# ESP32_BioReactor_v1.net
KiCad netlist of a schematic drawn in EAGLE
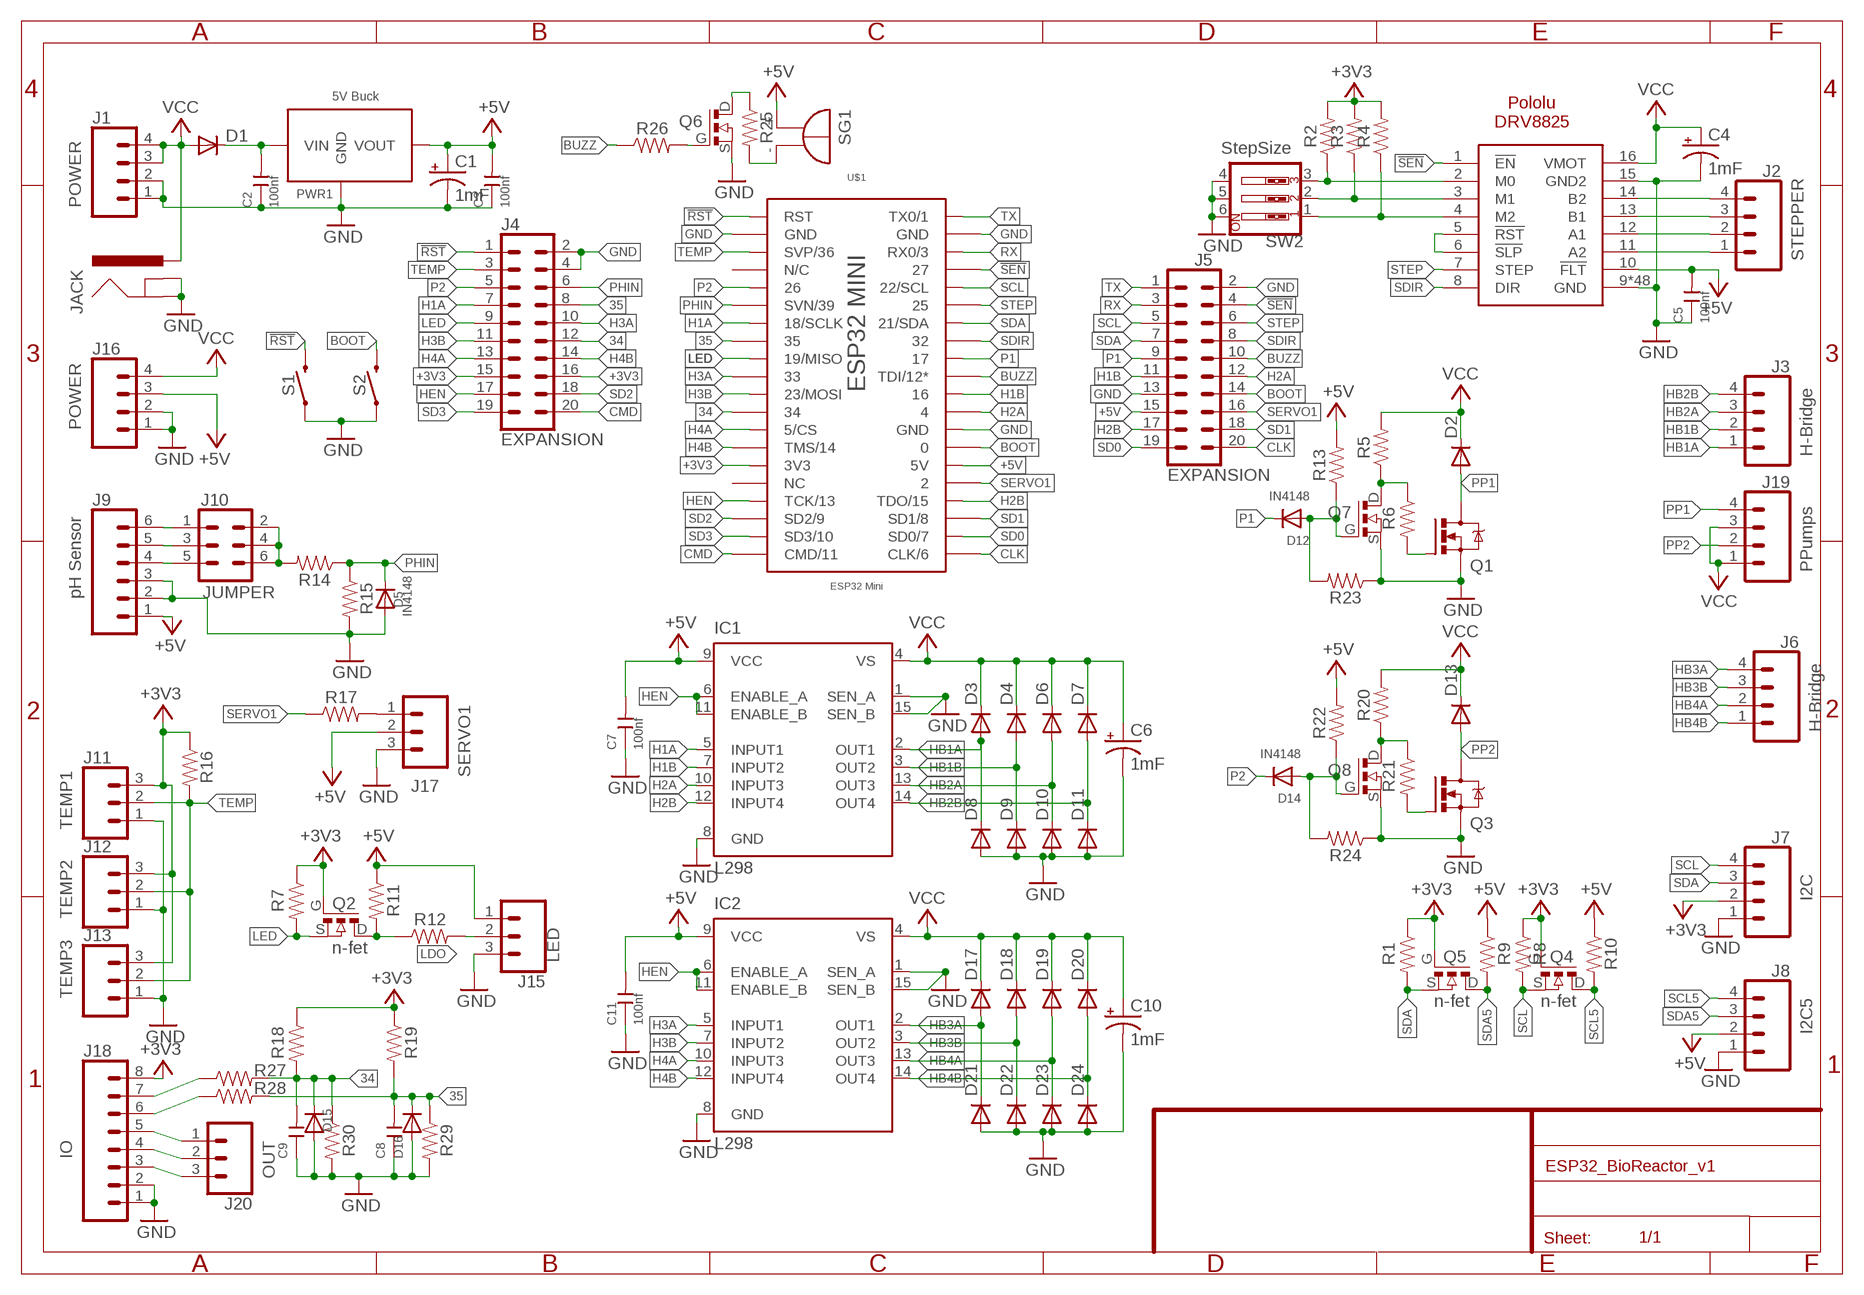
[diagram p0: schematic, sheet 1]

(export (version "E")
  (design (tool "Eeschema 10.0.6"))
  (components
    (comp (ref "C1")
      (value "1mF")
      (footprint "eagle-import:CPOL-RADIAL-5MM-10MM")
      (libsource (lib "eagle-import") (part "1000UF-RADIAL-5MM-25V-20%"))
    )
    (comp (ref "C2")
      (value "100nf")
      (footprint "eagle-import:CERAMIC-2.54")
      (fields (field (name "MPN") "CC1-F5SL2A101KSPW"))
      (libsource (lib "eagle-import") (part "DIP-CERAMIC-DISC-100NF-50V-Y5V(D5.0MM)"))
    )
    (comp (ref "C3")
      (value "100nf")
      (footprint "eagle-import:CERAMIC-2.54")
      (fields (field (name "MPN") "CC1-F5SL2A101KSPW"))
      (libsource (lib "eagle-import") (part "DIP-CERAMIC-DISC-100NF-50V-Y5V(D5.0MM)"))
    )
    (comp (ref "C4")
      (value "1mF")
      (footprint "eagle-import:CPOL-RADIAL-5MM-10MM")
      (libsource (lib "eagle-import") (part "1000UF-RADIAL-5MM-25V-20%"))
    )
    (comp (ref "C5")
      (value "100nf")
      (footprint "eagle-import:CERAMIC-2.54")
      (fields (field (name "MPN") "CC1-F5SL2A101KSPW"))
      (libsource (lib "eagle-import") (part "DIP-CERAMIC-DISC-100NF-50V-Y5V(D5.0MM)"))
    )
    (comp (ref "C6")
      (value "1mF")
      (footprint "eagle-import:CPOL-RADIAL-5MM-10MM")
      (libsource (lib "eagle-import") (part "1000UF-RADIAL-5MM-25V-20%"))
    )
    (comp (ref "C7")
      (value "100nf")
      (footprint "eagle-import:CERAMIC-2.54")
      (fields (field (name "MPN") "CC1-F5SL2A101KSPW"))
      (libsource (lib "eagle-import") (part "DIP-CERAMIC-DISC-100NF-50V-Y5V(D5.0MM)"))
    )
    (comp (ref "C8")
      (value "100nf")
      (footprint "eagle-import:CERAMIC-2.54")
      (fields (field (name "MPN") "CC1-F5SL2A101KSPW"))
      (libsource (lib "eagle-import") (part "DIP-CERAMIC-DISC-100NF-50V-Y5V(D5.0MM)"))
    )
    (comp (ref "C9")
      (value "100nf")
      (footprint "eagle-import:CERAMIC-2.54")
      (fields (field (name "MPN") "CC1-F5SL2A101KSPW"))
      (libsource (lib "eagle-import") (part "DIP-CERAMIC-DISC-100NF-50V-Y5V(D5.0MM)"))
    )
    (comp (ref "C10")
      (value "1mF")
      (footprint "eagle-import:CPOL-RADIAL-5MM-10MM")
      (libsource (lib "eagle-import") (part "1000UF-RADIAL-5MM-25V-20%"))
    )
    (comp (ref "C11")
      (value "100nf")
      (footprint "eagle-import:CERAMIC-2.54")
      (fields (field (name "MPN") "CC1-F5SL2A101KSPW"))
      (libsource (lib "eagle-import") (part "DIP-CERAMIC-DISC-100NF-50V-Y5V(D5.0MM)"))
    )
    (comp (ref "D1")
      (value "1N4004")
      (footprint "eagle-import:DO41-10")
      (libsource (lib "eagle-import") (part "1N4004"))
    )
    (comp (ref "D2")
      (value "1N4004")
      (footprint "eagle-import:DO41-10")
      (libsource (lib "eagle-import") (part "1N4004"))
    )
    (comp (ref "D3")
      (value "1N4004")
      (footprint "eagle-import:DO41-10")
      (libsource (lib "eagle-import") (part "1N4004"))
    )
    (comp (ref "D4")
      (value "1N4004")
      (footprint "eagle-import:DO41-10")
      (libsource (lib "eagle-import") (part "1N4004"))
    )
    (comp (ref "D5")
      (value "IN4148")
      (footprint "eagle-import:DO-1N4148")
      (libsource (lib "eagle-import") (part "DIODEDO-1N4148"))
    )
    (comp (ref "D6")
      (value "1N4004")
      (footprint "eagle-import:DO41-10")
      (libsource (lib "eagle-import") (part "1N4004"))
    )
    (comp (ref "D7")
      (value "1N4004")
      (footprint "eagle-import:DO41-10")
      (libsource (lib "eagle-import") (part "1N4004"))
    )
    (comp (ref "D8")
      (value "1N4004")
      (footprint "eagle-import:DO41-10")
      (libsource (lib "eagle-import") (part "1N4004"))
    )
    (comp (ref "D9")
      (value "1N4004")
      (footprint "eagle-import:DO41-10")
      (libsource (lib "eagle-import") (part "1N4004"))
    )
    (comp (ref "D10")
      (value "1N4004")
      (footprint "eagle-import:DO41-10")
      (libsource (lib "eagle-import") (part "1N4004"))
    )
    (comp (ref "D11")
      (value "1N4004")
      (footprint "eagle-import:DO41-10")
      (libsource (lib "eagle-import") (part "1N4004"))
    )
    (comp (ref "D12")
      (value "IN4148")
      (footprint "eagle-import:DO-1N4148")
      (libsource (lib "eagle-import") (part "DIODEDO-1N4148"))
    )
    (comp (ref "D13")
      (value "1N4004")
      (footprint "eagle-import:DO41-10")
      (libsource (lib "eagle-import") (part "1N4004"))
    )
    (comp (ref "D14")
      (value "IN4148")
      (footprint "eagle-import:DO-1N4148")
      (libsource (lib "eagle-import") (part "DIODEDO-1N4148"))
    )
    (comp (ref "D15")
      (value "IN4148")
      (footprint "eagle-import:DO-1N4148")
      (libsource (lib "eagle-import") (part "DIODEDO-1N4148"))
    )
    (comp (ref "D16")
      (value "IN4148")
      (footprint "eagle-import:DO-1N4148")
      (libsource (lib "eagle-import") (part "DIODEDO-1N4148"))
    )
    (comp (ref "D17")
      (value "1N4004")
      (footprint "eagle-import:DO41-10")
      (libsource (lib "eagle-import") (part "1N4004"))
    )
    (comp (ref "D18")
      (value "1N4004")
      (footprint "eagle-import:DO41-10")
      (libsource (lib "eagle-import") (part "1N4004"))
    )
    (comp (ref "D19")
      (value "1N4004")
      (footprint "eagle-import:DO41-10")
      (libsource (lib "eagle-import") (part "1N4004"))
    )
    (comp (ref "D20")
      (value "1N4004")
      (footprint "eagle-import:DO41-10")
      (libsource (lib "eagle-import") (part "1N4004"))
    )
    (comp (ref "D21")
      (value "1N4004")
      (footprint "eagle-import:DO41-10")
      (libsource (lib "eagle-import") (part "1N4004"))
    )
    (comp (ref "D22")
      (value "1N4004")
      (footprint "eagle-import:DO41-10")
      (libsource (lib "eagle-import") (part "1N4004"))
    )
    (comp (ref "D23")
      (value "1N4004")
      (footprint "eagle-import:DO41-10")
      (libsource (lib "eagle-import") (part "1N4004"))
    )
    (comp (ref "D24")
      (value "1N4004")
      (footprint "eagle-import:DO41-10")
      (libsource (lib "eagle-import") (part "1N4004"))
    )
    (comp (ref "DR1")
      (value "DRV8825")
      (footprint "eagle-import:POLOLU-DRV8825")
      (libsource (lib "eagle-import") (part "POLOLU-DRV8825"))
    )
    (comp (ref "IC1")
      (value "L298")
      (footprint "eagle-import:MULTIWATT-15")
      (fields (field (name "MPN") "L298N"))
      (libsource (lib "eagle-import") (part "L298"))
    )
    (comp (ref "IC2")
      (value "L298")
      (footprint "eagle-import:MULTIWATT-15")
      (fields (field (name "MPN") "L298N"))
      (libsource (lib "eagle-import") (part "L298"))
    )
    (comp (ref "J1")
      (value "POWER")
      (footprint "eagle-import:1X04_LONGPADS")
      (libsource (lib "eagle-import") (part "CONN_04LONGPADS"))
    )
    (comp (ref "J2")
      (value "STEPPER")
      (footprint "eagle-import:1X04_LONGPADS")
      (libsource (lib "eagle-import") (part "CONN_04LONGPADS"))
    )
    (comp (ref "J3")
      (value "H-Bridge")
      (footprint "eagle-import:1X04_LONGPADS")
      (libsource (lib "eagle-import") (part "CONN_04LONGPADS"))
    )
    (comp (ref "J4")
      (value "EXPANSION")
      (footprint "eagle-import:2X10_NOSILK")
      (libsource (lib "eagle-import") (part "CONN_10X2NOSILK"))
    )
    (comp (ref "J5")
      (value "EXPANSION")
      (footprint "eagle-import:2X10_NOSILK")
      (libsource (lib "eagle-import") (part "CONN_10X2NOSILK"))
    )
    (comp (ref "J6")
      (value "H-Bridge")
      (footprint "eagle-import:1X04_LONGPADS")
      (libsource (lib "eagle-import") (part "CONN_04LONGPADS"))
    )
    (comp (ref "J7")
      (value "I2C")
      (footprint "eagle-import:1X04_LONGPADS")
      (libsource (lib "eagle-import") (part "CONN_04LONGPADS"))
    )
    (comp (ref "J8")
      (value "I2C5")
      (footprint "eagle-import:1X04_LONGPADS")
      (libsource (lib "eagle-import") (part "CONN_04LONGPADS"))
    )
    (comp (ref "J9")
      (value "pH Sensor")
      (footprint "eagle-import:1X06_LONGPADS")
      (libsource (lib "eagle-import") (part "CONN_06LONGPADS"))
    )
    (comp (ref "J10")
      (value "JUMPER")
      (footprint "eagle-import:2X3")
      (libsource (lib "eagle-import") (part "CONN_03X2FEMALE"))
    )
    (comp (ref "J11")
      (value "TEMP1")
      (footprint "eagle-import:1X03_LONGPADS")
      (libsource (lib "eagle-import") (part "CONN_03LONGPADS"))
    )
    (comp (ref "J12")
      (value "TEMP2")
      (footprint "eagle-import:1X03_LONGPADS")
      (libsource (lib "eagle-import") (part "CONN_03LONGPADS"))
    )
    (comp (ref "J13")
      (value "TEMP3")
      (footprint "eagle-import:1X03_LONGPADS")
      (libsource (lib "eagle-import") (part "CONN_03LONGPADS"))
    )
    (comp (ref "J15")
      (value "LED")
      (footprint "eagle-import:1X03_LONGPADS")
      (libsource (lib "eagle-import") (part "CONN_03LONGPADS"))
    )
    (comp (ref "J16")
      (value "POWER")
      (footprint "eagle-import:1X04_LONGPADS")
      (libsource (lib "eagle-import") (part "CONN_04LONGPADS"))
    )
    (comp (ref "J17")
      (value "SERVO1")
      (footprint "eagle-import:1X03_LONGPADS")
      (libsource (lib "eagle-import") (part "CONN_03LONGPADS"))
    )
    (comp (ref "J18")
      (value "IO")
      (footprint "eagle-import:1X08_LONGPADS")
      (libsource (lib "eagle-import") (part "CONN_08LONGPADS"))
    )
    (comp (ref "J19")
      (value "PPumps")
      (footprint "eagle-import:1X04_LONGPADS")
      (libsource (lib "eagle-import") (part "CONN_04LONGPADS"))
    )
    (comp (ref "J20")
      (value "OUT")
      (footprint "eagle-import:1X03")
      (libsource (lib "eagle-import") (part "CONN_03"))
    )
    (comp (ref "JACK")
      (value "POWER_JACKPTH_LOCK")
      (footprint "eagle-import:POWER_JACK_PTH_LOCK")
      (libsource (lib "eagle-import") (part "POWER_JACKPTH_LOCK"))
    )
    (comp (ref "PWR1")
      (value "5V Buck")
      (footprint "eagle-import:5VBUCK")
      (libsource (lib "eagle-import") (part "5VBUCK"))
    )
    (comp (ref "Q1")
      (value "IRF740")
      (footprint "eagle-import:TO220BV")
      (libsource (lib "eagle-import") (part "IRF740"))
    )
    (comp (ref "Q2")
      (value "n-fet")
      (footprint "eagle-import:TO92260P520H533-3")
      (fields (field (name "MF") "STMicroelectronics") (field (name "MP") "2N7000"))
      (libsource (lib "eagle-import") (part "2N7000"))
    )
    (comp (ref "Q3")
      (value "IRF740")
      (footprint "eagle-import:TO220BV")
      (libsource (lib "eagle-import") (part "IRF740"))
    )
    (comp (ref "Q4")
      (value "n-fet")
      (footprint "eagle-import:TO92260P520H533-3")
      (fields (field (name "MF") "STMicroelectronics") (field (name "MP") "2N7000"))
      (libsource (lib "eagle-import") (part "2N7000"))
    )
    (comp (ref "Q5")
      (value "n-fet")
      (footprint "eagle-import:TO92260P520H533-3")
      (fields (field (name "MF") "STMicroelectronics") (field (name "MP") "2N7000"))
      (libsource (lib "eagle-import") (part "2N7000"))
    )
    (comp (ref "Q6")
      (value "2N7000")
      (footprint "eagle-import:TO92260P520H533-3")
      (fields (field (name "MF") "STMicroelectronics"))
      (libsource (lib "eagle-import") (part "2N7000"))
    )
    (comp (ref "Q7")
      (value "2N7000")
      (footprint "eagle-import:TO92260P520H533-3")
      (fields (field (name "MF") "STMicroelectronics"))
      (libsource (lib "eagle-import") (part "2N7000"))
    )
    (comp (ref "Q8")
      (value "2N7000")
      (footprint "eagle-import:TO92260P520H533-3")
      (fields (field (name "MF") "STMicroelectronics"))
      (libsource (lib "eagle-import") (part "2N7000"))
    )
    (comp (ref "R1")
      (value "10k")
      (footprint "eagle-import:AXIAL-0.3")
      (libsource (lib "eagle-import") (part "10KOHM-HORIZ-1/4W-1%"))
    )
    (comp (ref "R2")
      (value "10k")
      (footprint "eagle-import:AXIAL-0.3")
      (libsource (lib "eagle-import") (part "10KOHM-HORIZ-1/4W-1%"))
    )
    (comp (ref "R3")
      (value "10k")
      (footprint "eagle-import:AXIAL-0.3")
      (libsource (lib "eagle-import") (part "10KOHM-HORIZ-1/4W-1%"))
    )
    (comp (ref "R4")
      (value "10k")
      (footprint "eagle-import:AXIAL-0.3")
      (libsource (lib "eagle-import") (part "10KOHM-HORIZ-1/4W-1%"))
    )
    (comp (ref "R5")
      (value "10k")
      (footprint "eagle-import:AXIAL-0.3")
      (libsource (lib "eagle-import") (part "10KOHM-HORIZ-1/4W-1%"))
    )
    (comp (ref "R6")
      (value "10k")
      (footprint "eagle-import:AXIAL-0.3")
      (libsource (lib "eagle-import") (part "10KOHM-HORIZ-1/4W-1%"))
    )
    (comp (ref "R7")
      (value "10k")
      (footprint "eagle-import:AXIAL-0.3")
      (libsource (lib "eagle-import") (part "10KOHM-HORIZ-1/4W-1%"))
    )
    (comp (ref "R8")
      (value "10k")
      (footprint "eagle-import:AXIAL-0.3")
      (libsource (lib "eagle-import") (part "10KOHM-HORIZ-1/4W-1%"))
    )
    (comp (ref "R9")
      (value "10k")
      (footprint "eagle-import:AXIAL-0.3")
      (libsource (lib "eagle-import") (part "10KOHM-HORIZ-1/4W-1%"))
    )
    (comp (ref "R10")
      (value "10k")
      (footprint "eagle-import:AXIAL-0.3")
      (libsource (lib "eagle-import") (part "10KOHM-HORIZ-1/4W-1%"))
    )
    (comp (ref "R11")
      (value "10k")
      (footprint "eagle-import:AXIAL-0.3")
      (libsource (lib "eagle-import") (part "10KOHM-HORIZ-1/4W-1%"))
    )
    (comp (ref "R12")
      (value "10k")
      (footprint "eagle-import:AXIAL-0.3")
      (libsource (lib "eagle-import") (part "10KOHM-HORIZ-1/4W-1%"))
    )
    (comp (ref "R13")
      (value "10k")
      (footprint "eagle-import:AXIAL-0.3")
      (libsource (lib "eagle-import") (part "10KOHM-HORIZ-1/4W-1%"))
    )
    (comp (ref "R14")
      (value "10k")
      (footprint "eagle-import:AXIAL-0.3")
      (libsource (lib "eagle-import") (part "10KOHM-HORIZ-1/4W-1%"))
    )
    (comp (ref "R15")
      (value "10k")
      (footprint "eagle-import:AXIAL-0.3")
      (libsource (lib "eagle-import") (part "10KOHM-HORIZ-1/4W-1%"))
    )
    (comp (ref "R16")
      (value "10k")
      (footprint "eagle-import:AXIAL-0.3")
      (libsource (lib "eagle-import") (part "10KOHM-HORIZ-1/4W-1%"))
    )
    (comp (ref "R17")
      (value "10k")
      (footprint "eagle-import:AXIAL-0.3")
      (libsource (lib "eagle-import") (part "10KOHM-HORIZ-1/4W-1%"))
    )
    (comp (ref "R18")
      (value "10k")
      (footprint "eagle-import:AXIAL-0.3")
      (libsource (lib "eagle-import") (part "10KOHM-HORIZ-1/4W-1%"))
    )
    (comp (ref "R19")
      (value "10k")
      (footprint "eagle-import:AXIAL-0.3")
      (libsource (lib "eagle-import") (part "10KOHM-HORIZ-1/4W-1%"))
    )
    (comp (ref "R20")
      (value "10k")
      (footprint "eagle-import:AXIAL-0.3")
      (libsource (lib "eagle-import") (part "10KOHM-HORIZ-1/4W-1%"))
    )
    (comp (ref "R21")
      (value "10k")
      (footprint "eagle-import:AXIAL-0.3")
      (libsource (lib "eagle-import") (part "10KOHM-HORIZ-1/4W-1%"))
    )
    (comp (ref "R22")
      (value "10k")
      (footprint "eagle-import:AXIAL-0.3")
      (libsource (lib "eagle-import") (part "10KOHM-HORIZ-1/4W-1%"))
    )
    (comp (ref "R23")
      (value "10k")
      (footprint "eagle-import:AXIAL-0.3")
      (libsource (lib "eagle-import") (part "10KOHM-HORIZ-1/4W-1%"))
    )
    (comp (ref "R24")
      (value "10k")
      (footprint "eagle-import:AXIAL-0.3")
      (libsource (lib "eagle-import") (part "10KOHM-HORIZ-1/4W-1%"))
    )
    (comp (ref "R25")
      (value "10k")
      (footprint "eagle-import:AXIAL-0.3")
      (libsource (lib "eagle-import") (part "10KOHM-HORIZ-1/4W-1%"))
    )
    (comp (ref "R26")
      (value "10k")
      (footprint "eagle-import:AXIAL-0.3")
      (libsource (lib "eagle-import") (part "10KOHM-HORIZ-1/4W-1%"))
    )
    (comp (ref "R27")
      (value "10k")
      (footprint "eagle-import:AXIAL-0.3")
      (libsource (lib "eagle-import") (part "10KOHM-HORIZ-1/4W-1%"))
    )
    (comp (ref "R28")
      (value "10k")
      (footprint "eagle-import:AXIAL-0.3")
      (libsource (lib "eagle-import") (part "10KOHM-HORIZ-1/4W-1%"))
    )
    (comp (ref "R29")
      (value "10k")
      (footprint "eagle-import:AXIAL-0.3")
      (libsource (lib "eagle-import") (part "10KOHM-HORIZ-1/4W-1%"))
    )
    (comp (ref "R30")
      (value "10k")
      (footprint "eagle-import:AXIAL-0.3")
      (libsource (lib "eagle-import") (part "10KOHM-HORIZ-1/4W-1%"))
    )
    (comp (ref "S1")
      (value "MOMENTARY-SWITCH-SPST-PTH-6.0MM")
      (footprint "eagle-import:TACTILE_SWITCH_PTH_6.0MM")
      (libsource (lib "eagle-import") (part "MOMENTARY-SWITCH-SPST-PTH-6.0MM"))
    )
    (comp (ref "S2")
      (value "MOMENTARY-SWITCH-SPST-PTH-6.0MM")
      (footprint "eagle-import:TACTILE_SWITCH_PTH_6.0MM")
      (libsource (lib "eagle-import") (part "MOMENTARY-SWITCH-SPST-PTH-6.0MM"))
    )
    (comp (ref "SG1")
      (value "F/HMB")
      (footprint "eagle-import:F_HMB")
      (libsource (lib "eagle-import") (part "F/HMB"))
    )
    (comp (ref "SW2")
      (value "StepSize")
      (footprint "eagle-import:EDG-03")
      (libsource (lib "eagle-import") (part "SW_DIP-3"))
    )
    (comp (ref "U$1")
      (value "ESP32 Mini")
      (footprint "eagle-import:ESP32MINI")
      (libsource (lib "eagle-import") (part "ESP32MINI"))
    )
  )
  (nets
    (net (code "1") (name "+3V3") (class "Default")
      (node (ref "J11") (pin "3") (pinfunction "3_3") (pintype "passive"))
      (node (ref "J12") (pin "3") (pinfunction "3_3") (pintype "passive"))
      (node (ref "J13") (pin "3") (pinfunction "3_3") (pintype "passive"))
      (node (ref "J18") (pin "8") (pinfunction "8_8") (pintype "passive"))
      (node (ref "J4") (pin "15") (pinfunction "15_15") (pintype "passive"))
      (node (ref "J4") (pin "16") (pinfunction "16_16") (pintype "passive"))
      (node (ref "J7") (pin "2") (pinfunction "2_2") (pintype "passive"))
      (node (ref "Q2") (pin "G") (pinfunction "G_G") (pintype "bidirectional"))
      (node (ref "Q4") (pin "G") (pinfunction "G_G") (pintype "bidirectional"))
      (node (ref "Q5") (pin "G") (pinfunction "G_G") (pintype "bidirectional"))
      (node (ref "R1") (pin "P$1") (pinfunction "1_P$1") (pintype "passive"))
      (node (ref "R16") (pin "P$1") (pinfunction "1_P$1") (pintype "passive"))
      (node (ref "R18") (pin "P$1") (pinfunction "1_P$1") (pintype "passive"))
      (node (ref "R19") (pin "P$1") (pinfunction "1_P$1") (pintype "passive"))
      (node (ref "R2") (pin "P$2") (pinfunction "2_P$2") (pintype "passive"))
      (node (ref "R3") (pin "P$2") (pinfunction "2_P$2") (pintype "passive"))
      (node (ref "R4") (pin "P$2") (pinfunction "2_P$2") (pintype "passive"))
      (node (ref "R7") (pin "P$1") (pinfunction "1_P$1") (pintype "passive"))
      (node (ref "R8") (pin "P$1") (pinfunction "1_P$1") (pintype "passive"))
      (node (ref "U$1") (pin "3V3") (pinfunction "3V3_3V3") (pintype "power_in"))
    )
    (net (code "2") (name "+5V") (class "Default")
      (node (ref "C1") (pin "+") (pinfunction "+_+") (pintype "passive"))
      (node (ref "C11") (pin "2") (pinfunction "2_2") (pintype "passive"))
      (node (ref "C3") (pin "2") (pinfunction "2_2") (pintype "passive"))
      (node (ref "C5") (pin "2") (pinfunction "2_2") (pintype "passive"))
      (node (ref "C7") (pin "2") (pinfunction "2_2") (pintype "passive"))
      (node (ref "DR1") (pin "10") (pinfunction "~{FLT}_10") (pintype "bidirectional"))
      (node (ref "IC1") (pin "9") (pinfunction "VCC_9") (pintype "power_in"))
      (node (ref "IC2") (pin "9") (pinfunction "VCC_9") (pintype "power_in"))
      (node (ref "J15") (pin "1") (pinfunction "1_1") (pintype "passive"))
      (node (ref "J16") (pin "3") (pinfunction "3_3") (pintype "passive"))
      (node (ref "J17") (pin "2") (pinfunction "2_2") (pintype "passive"))
      (node (ref "J5") (pin "15") (pinfunction "15_15") (pintype "passive"))
      (node (ref "J8") (pin "2") (pinfunction "2_2") (pintype "passive"))
      (node (ref "J9") (pin "1") (pinfunction "1_1") (pintype "passive"))
      (node (ref "PWR1") (pin "VOUT") (pinfunction "VOUT_VOUT") (pintype "bidirectional"))
      (node (ref "R10") (pin "P$1") (pinfunction "1_P$1") (pintype "passive"))
      (node (ref "R11") (pin "P$1") (pinfunction "1_P$1") (pintype "passive"))
      (node (ref "R13") (pin "P$2") (pinfunction "2_P$2") (pintype "passive"))
      (node (ref "R22") (pin "P$2") (pinfunction "2_P$2") (pintype "passive"))
      (node (ref "R9") (pin "P$1") (pinfunction "1_P$1") (pintype "passive"))
      (node (ref "SG1") (pin "+") (pinfunction "+_+") (pintype "passive"))
      (node (ref "U$1") (pin "5V") (pinfunction "5V_5V") (pintype "power_in"))
    )
    (net (code "3") (name "/~{RST}") (class "Default")
      (node (ref "J4") (pin "1") (pinfunction "1_1") (pintype "passive"))
      (node (ref "S1") (pin "3") (pinfunction "2_3") (pintype "passive"))
      (node (ref "U$1") (pin "RST") (pinfunction "RST_RST") (pintype "bidirectional"))
    )
    (net (code "4") (name "/~{SEN}") (class "Default")
      (node (ref "DR1") (pin "1") (pinfunction "~{EN}_1") (pintype "bidirectional"))
      (node (ref "J5") (pin "4") (pinfunction "4_4") (pintype "passive"))
      (node (ref "U$1") (pin "27") (pinfunction "27_27") (pintype "bidirectional"))
    )
    (net (code "5") (name "34") (class "Default")
      (node (ref "C9") (pin "2") (pinfunction "2_2") (pintype "passive"))
      (node (ref "D15") (pin "C") (pinfunction "C_C") (pintype "passive"))
      (node (ref "J4") (pin "12") (pinfunction "12_12") (pintype "passive"))
      (node (ref "R18") (pin "P$2") (pinfunction "2_P$2") (pintype "passive"))
      (node (ref "R27") (pin "P$2") (pinfunction "2_P$2") (pintype "passive"))
      (node (ref "R30") (pin "P$1") (pinfunction "1_P$1") (pintype "passive"))
      (node (ref "U$1") (pin "34") (pinfunction "34_34") (pintype "bidirectional"))
    )
    (net (code "6") (name "35") (class "Default")
      (node (ref "C8") (pin "2") (pinfunction "2_2") (pintype "passive"))
      (node (ref "D16") (pin "C") (pinfunction "C_C") (pintype "passive"))
      (node (ref "J4") (pin "8") (pinfunction "8_8") (pintype "passive"))
      (node (ref "R19") (pin "P$2") (pinfunction "2_P$2") (pintype "passive"))
      (node (ref "R28") (pin "P$2") (pinfunction "2_P$2") (pintype "passive"))
      (node (ref "R29") (pin "P$1") (pinfunction "1_P$1") (pintype "passive"))
      (node (ref "U$1") (pin "35") (pinfunction "35_35") (pintype "bidirectional"))
    )
    (net (code "7") (name "BOOT") (class "Default")
      (node (ref "J5") (pin "14") (pinfunction "14_14") (pintype "passive"))
      (node (ref "S2") (pin "3") (pinfunction "2_3") (pintype "passive"))
      (node (ref "U$1") (pin "0") (pinfunction "0_0") (pintype "bidirectional"))
    )
    (net (code "8") (name "BUZZ") (class "Default")
      (node (ref "J5") (pin "10") (pinfunction "10_10") (pintype "passive"))
      (node (ref "R26") (pin "P$1") (pinfunction "1_P$1") (pintype "passive"))
      (node (ref "U$1") (pin "TDI") (pinfunction "TDI/12*_TDI") (pintype "bidirectional"))
    )
    (net (code "9") (name "CLK") (class "Default")
      (node (ref "J5") (pin "20") (pinfunction "20_20") (pintype "passive"))
      (node (ref "U$1") (pin "CLK") (pinfunction "CLK/6_CLK") (pintype "bidirectional"))
    )
    (net (code "10") (name "CMD") (class "Default")
      (node (ref "J4") (pin "20") (pinfunction "20_20") (pintype "passive"))
      (node (ref "U$1") (pin "CMD") (pinfunction "CMD/11_CMD") (pintype "bidirectional"))
    )
    (net (code "11") (name "GND") (class "Default")
      (node (ref "C1") (pin "-") (pinfunction "-_-") (pintype "passive"))
      (node (ref "C10") (pin "-") (pinfunction "-_-") (pintype "passive"))
      (node (ref "C11") (pin "1") (pinfunction "1_1") (pintype "passive"))
      (node (ref "C2") (pin "1") (pinfunction "1_1") (pintype "passive"))
      (node (ref "C3") (pin "1") (pinfunction "1_1") (pintype "passive"))
      (node (ref "C4") (pin "-") (pinfunction "-_-") (pintype "passive"))
      (node (ref "C5") (pin "1") (pinfunction "1_1") (pintype "passive"))
      (node (ref "C6") (pin "-") (pinfunction "-_-") (pintype "passive"))
      (node (ref "C7") (pin "1") (pinfunction "1_1") (pintype "passive"))
      (node (ref "C8") (pin "1") (pinfunction "1_1") (pintype "passive"))
      (node (ref "C9") (pin "1") (pinfunction "1_1") (pintype "passive"))
      (node (ref "D10") (pin "A") (pinfunction "A_A") (pintype "passive"))
      (node (ref "D11") (pin "A") (pinfunction "A_A") (pintype "passive"))
      (node (ref "D15") (pin "A") (pinfunction "A_A") (pintype "passive"))
      (node (ref "D16") (pin "A") (pinfunction "A_A") (pintype "passive"))
      (node (ref "D21") (pin "A") (pinfunction "A_A") (pintype "passive"))
      (node (ref "D22") (pin "A") (pinfunction "A_A") (pintype "passive"))
      (node (ref "D23") (pin "A") (pinfunction "A_A") (pintype "passive"))
      (node (ref "D24") (pin "A") (pinfunction "A_A") (pintype "passive"))
      (node (ref "D5") (pin "A") (pinfunction "A_A") (pintype "passive"))
      (node (ref "D8") (pin "A") (pinfunction "A_A") (pintype "passive"))
      (node (ref "D9") (pin "A") (pinfunction "A_A") (pintype "passive"))
      (node (ref "DR1") (pin "15") (pinfunction "GND2_15") (pintype "bidirectional"))
      (node (ref "DR1") (pin "9") (pinfunction "GND_9") (pintype "bidirectional"))
      (node (ref "DR1") (pin "GND@1") (pinfunction "GND_GND@1") (pintype "bidirectional"))
      (node (ref "DR1") (pin "GND@10") (pinfunction "GND_GND@10") (pintype "bidirectional"))
      (node (ref "DR1") (pin "GND@11") (pinfunction "GND_GND@11") (pintype "bidirectional"))
      (node (ref "DR1") (pin "GND@12") (pinfunction "GND_GND@12") (pintype "bidirectional"))
      (node (ref "DR1") (pin "GND@13") (pinfunction "GND_GND@13") (pintype "bidirectional"))
      (node (ref "DR1") (pin "GND@14") (pinfunction "GND_GND@14") (pintype "bidirectional"))
      (node (ref "DR1") (pin "GND@15") (pinfunction "GND_GND@15") (pintype "bidirectional"))
      (node (ref "DR1") (pin "GND@16") (pinfunction "GND_GND@16") (pintype "bidirectional"))
      (node (ref "DR1") (pin "GND@17") (pinfunction "GND_GND@17") (pintype "bidirectional"))
      (node (ref "DR1") (pin "GND@18") (pinfunction "GND_GND@18") (pintype "bidirectional"))
      (node (ref "DR1") (pin "GND@19") (pinfunction "GND_GND@19") (pintype "bidirectional"))
      (node (ref "DR1") (pin "GND@2") (pinfunction "GND_GND@2") (pintype "bidirectional"))
      (node (ref "DR1") (pin "GND@20") (pinfunction "GND_GND@20") (pintype "bidirectional"))
      (node (ref "DR1") (pin "GND@21") (pinfunction "GND_GND@21") (pintype "bidirectional"))
      (node (ref "DR1") (pin "GND@22") (pinfunction "GND_GND@22") (pintype "bidirectional"))
      (node (ref "DR1") (pin "GND@23") (pinfunction "GND_GND@23") (pintype "bidirectional"))
      (node (ref "DR1") (pin "GND@24") (pinfunction "GND_GND@24") (pintype "bidirectional"))
      (node (ref "DR1") (pin "GND@25") (pinfunction "GND_GND@25") (pintype "bidirectional"))
      (node (ref "DR1") (pin "GND@26") (pinfunction "GND_GND@26") (pintype "bidirectional"))
      (node (ref "DR1") (pin "GND@27") (pinfunction "GND_GND@27") (pintype "bidirectional"))
      (node (ref "DR1") (pin "GND@28") (pinfunction "GND_GND@28") (pintype "bidirectional"))
      (node (ref "DR1") (pin "GND@29") (pinfunction "GND_GND@29") (pintype "bidirectional"))
      (node (ref "DR1") (pin "GND@3") (pinfunction "GND_GND@3") (pintype "bidirectional"))
      (node (ref "DR1") (pin "GND@30") (pinfunction "GND_GND@30") (pintype "bidirectional"))
      (node (ref "DR1") (pin "GND@31") (pinfunction "GND_GND@31") (pintype "bidirectional"))
      (node (ref "DR1") (pin "GND@32") (pinfunction "GND_GND@32") (pintype "bidirectional"))
      (node (ref "DR1") (pin "GND@33") (pinfunction "GND_GND@33") (pintype "bidirectional"))
      (node (ref "DR1") (pin "GND@34") (pinfunction "GND_GND@34") (pintype "bidirectional"))
      (node (ref "DR1") (pin "GND@35") (pinfunction "GND_GND@35") (pintype "bidirectional"))
      (node (ref "DR1") (pin "GND@36") (pinfunction "GND_GND@36") (pintype "bidirectional"))
      (node (ref "DR1") (pin "GND@37") (pinfunction "GND_GND@37") (pintype "bidirectional"))
      (node (ref "DR1") (pin "GND@38") (pinfunction "GND_GND@38") (pintype "bidirectional"))
      (node (ref "DR1") (pin "GND@39") (pinfunction "GND_GND@39") (pintype "bidirectional"))
      (node (ref "DR1") (pin "GND@4") (pinfunction "GND_GND@4") (pintype "bidirectional"))
      (node (ref "DR1") (pin "GND@40") (pinfunction "GND_GND@40") (pintype "bidirectional"))
      (node (ref "DR1") (pin "GND@41") (pinfunction "GND_GND@41") (pintype "bidirectional"))
      (node (ref "DR1") (pin "GND@42") (pinfunction "GND_GND@42") (pintype "bidirectional"))
      (node (ref "DR1") (pin "GND@43") (pinfunction "GND_GND@43") (pintype "bidirectional"))
      (node (ref "DR1") (pin "GND@44") (pinfunction "GND_GND@44") (pintype "bidirectional"))
      (node (ref "DR1") (pin "GND@45") (pinfunction "GND_GND@45") (pintype "bidirectional"))
      (node (ref "DR1") (pin "GND@5") (pinfunction "GND_GND@5") (pintype "bidirectional"))
      (node (ref "DR1") (pin "GND@50") (pinfunction "GND_GND@50") (pintype "bidirectional"))
      (node (ref "DR1") (pin "GND@51") (pinfunction "GND_GND@51") (pintype "bidirectional"))
      (node (ref "DR1") (pin "GND@6") (pinfunction "GND_GND@6") (pintype "bidirectional"))
      (node (ref "DR1") (pin "GND@7") (pinfunction "GND_GND@7") (pintype "bidirectional"))
      (node (ref "DR1") (pin "GND@8") (pinfunction "GND_GND@8") (pintype "bidirectional"))
      (node (ref "DR1") (pin "GND@9") (pinfunction "GND_GND@9") (pintype "bidirectional"))
      (node (ref "IC1") (pin "1") (pinfunction "SEN_A_1") (pintype "input"))
      (node (ref "IC1") (pin "15") (pinfunction "SEN_B_15") (pintype "input"))
      (node (ref "IC1") (pin "8") (pinfunction "GND_8") (pintype "power_in"))
      (node (ref "IC2") (pin "1") (pinfunction "SEN_A_1") (pintype "input"))
      (node (ref "IC2") (pin "15") (pinfunction "SEN_B_15") (pintype "input"))
      (node (ref "IC2") (pin "8") (pinfunction "GND_8") (pintype "power_in"))
      (node (ref "J1") (pin "1") (pinfunction "1_1") (pintype "passive"))
      (node (ref "J1") (pin "2") (pinfunction "2_2") (pintype "passive"))
      (node (ref "J11") (pin "1") (pinfunction "1_1") (pintype "passive"))
      (node (ref "J12") (pin "1") (pinfunction "1_1") (pintype "passive"))
      (node (ref "J13") (pin "1") (pinfunction "1_1") (pintype "passive"))
      (node (ref "J15") (pin "3") (pinfunction "3_3") (pintype "passive"))
      (node (ref "J16") (pin "1") (pinfunction "1_1") (pintype "passive"))
      (node (ref "J16") (pin "2") (pinfunction "2_2") (pintype "passive"))
      (node (ref "J17") (pin "3") (pinfunction "3_3") (pintype "passive"))
      (node (ref "J18") (pin "1") (pinfunction "1_1") (pintype "passive"))
      (node (ref "J18") (pin "2") (pinfunction "2_2") (pintype "passive"))
      (node (ref "J4") (pin "2") (pinfunction "2_2") (pintype "passive"))
      (node (ref "J4") (pin "4") (pinfunction "4_4") (pintype "passive"))
      (node (ref "J5") (pin "13") (pinfunction "13_13") (pintype "passive"))
      (node (ref "J5") (pin "2") (pinfunction "2_2") (pintype "passive"))
      (node (ref "J7") (pin "1") (pinfunction "1_1") (pintype "passive"))
      (node (ref "J8") (pin "1") (pinfunction "1_1") (pintype "passive"))
      (node (ref "J9") (pin "2") (pinfunction "2_2") (pintype "passive"))
      (node (ref "J9") (pin "3") (pinfunction "3_3") (pintype "passive"))
      (node (ref "JACK") (pin "GND") (pinfunction "GND_GND") (pintype "bidirectional"))
      (node (ref "JACK") (pin "GNDBREAK") (pinfunction "GNDBREAK_GNDBREAK") (pintype "bidirectional"))
      (node (ref "PWR1") (pin "GND") (pinfunction "GND_GND") (pintype "bidirectional"))
      (node (ref "Q1") (pin "S") (pinfunction "S_S") (pintype "passive"))
      (node (ref "Q3") (pin "S") (pinfunction "S_S") (pintype "passive"))
      (node (ref "Q6") (pin "S") (pinfunction "S_S") (pintype "bidirectional"))
      (node (ref "Q7") (pin "S") (pinfunction "S_S") (pintype "bidirectional"))
      (node (ref "Q8") (pin "S") (pinfunction "S_S") (pintype "bidirectional"))
      (node (ref "R15") (pin "P$2") (pinfunction "2_P$2") (pintype "passive"))
      (node (ref "R23") (pin "P$1") (pinfunction "1_P$1") (pintype "passive"))
      (node (ref "R24") (pin "P$1") (pinfunction "1_P$1") (pintype "passive"))
      (node (ref "R29") (pin "P$2") (pinfunction "2_P$2") (pintype "passive"))
      (node (ref "R30") (pin "P$2") (pinfunction "2_P$2") (pintype "passive"))
      (node (ref "S1") (pin "1") (pinfunction "1_1") (pintype "passive"))
      (node (ref "S2") (pin "1") (pinfunction "1_1") (pintype "passive"))
      (node (ref "SW2") (pin "4") (pinfunction "4_4") (pintype "passive"))
      (node (ref "SW2") (pin "5") (pinfunction "5_5") (pintype "passive"))
      (node (ref "SW2") (pin "6") (pinfunction "6_6") (pintype "passive"))
      (node (ref "U$1") (pin "GND@1") (pinfunction "GND_GND@1") (pintype "power_in"))
      (node (ref "U$1") (pin "GND@2") (pinfunction "GND_GND@2") (pintype "power_in"))
      (node (ref "U$1") (pin "GND@3") (pinfunction "GND_GND@3") (pintype "power_in"))
    )
    (net (code "12") (name "H1A") (class "Default")
      (node (ref "IC1") (pin "5") (pinfunction "INPUT1_5") (pintype "input"))
      (node (ref "J4") (pin "7") (pinfunction "7_7") (pintype "passive"))
      (node (ref "U$1") (pin "18") (pinfunction "18/SCLK_18") (pintype "bidirectional"))
    )
    (net (code "13") (name "H1B") (class "Default")
      (node (ref "IC1") (pin "7") (pinfunction "INPUT2_7") (pintype "input"))
      (node (ref "J5") (pin "11") (pinfunction "11_11") (pintype "passive"))
      (node (ref "U$1") (pin "16") (pinfunction "16_16") (pintype "bidirectional"))
    )
    (net (code "14") (name "H2A") (class "Default")
      (node (ref "IC1") (pin "10") (pinfunction "INPUT3_10") (pintype "input"))
      (node (ref "J5") (pin "12") (pinfunction "12_12") (pintype "passive"))
      (node (ref "U$1") (pin "4") (pinfunction "4_4") (pintype "bidirectional"))
    )
    (net (code "15") (name "H2B") (class "Default")
      (node (ref "IC1") (pin "12") (pinfunction "INPUT4_12") (pintype "input"))
      (node (ref "J5") (pin "17") (pinfunction "17_17") (pintype "passive"))
      (node (ref "U$1") (pin "TDO") (pinfunction "TDO/15_TDO") (pintype "bidirectional"))
    )
    (net (code "16") (name "H3A") (class "Default")
      (node (ref "IC2") (pin "5") (pinfunction "INPUT1_5") (pintype "input"))
      (node (ref "J4") (pin "10") (pinfunction "10_10") (pintype "passive"))
      (node (ref "U$1") (pin "33") (pinfunction "33_33") (pintype "bidirectional"))
    )
    (net (code "17") (name "H3B") (class "Default")
      (node (ref "IC2") (pin "7") (pinfunction "INPUT2_7") (pintype "input"))
      (node (ref "J4") (pin "11") (pinfunction "11_11") (pintype "passive"))
      (node (ref "U$1") (pin "23") (pinfunction "23/MOSI_23") (pintype "bidirectional"))
    )
    (net (code "18") (name "H4A") (class "Default")
      (node (ref "IC2") (pin "10") (pinfunction "INPUT3_10") (pintype "input"))
      (node (ref "J4") (pin "13") (pinfunction "13_13") (pintype "passive"))
      (node (ref "U$1") (pin "5") (pinfunction "5/CS_5") (pintype "bidirectional"))
    )
    (net (code "19") (name "H4B") (class "Default")
      (node (ref "IC2") (pin "12") (pinfunction "INPUT4_12") (pintype "input"))
      (node (ref "J4") (pin "14") (pinfunction "14_14") (pintype "passive"))
      (node (ref "U$1") (pin "TMS") (pinfunction "TMS/14_TMS") (pintype "bidirectional"))
    )
    (net (code "20") (name "HB1A") (class "Default")
      (node (ref "D3") (pin "A") (pinfunction "A_A") (pintype "passive"))
      (node (ref "D8") (pin "C") (pinfunction "C_C") (pintype "passive"))
      (node (ref "IC1") (pin "2") (pinfunction "OUT1_2") (pintype "output"))
      (node (ref "J3") (pin "1") (pinfunction "1_1") (pintype "passive"))
    )
    (net (code "21") (name "HB1B") (class "Default")
      (node (ref "D4") (pin "A") (pinfunction "A_A") (pintype "passive"))
      (node (ref "D9") (pin "C") (pinfunction "C_C") (pintype "passive"))
      (node (ref "IC1") (pin "3") (pinfunction "OUT2_3") (pintype "output"))
      (node (ref "J3") (pin "2") (pinfunction "2_2") (pintype "passive"))
    )
    (net (code "22") (name "HB2A") (class "Default")
      (node (ref "D10") (pin "C") (pinfunction "C_C") (pintype "passive"))
      (node (ref "D6") (pin "A") (pinfunction "A_A") (pintype "passive"))
      (node (ref "IC1") (pin "13") (pinfunction "OUT3_13") (pintype "output"))
      (node (ref "J3") (pin "3") (pinfunction "3_3") (pintype "passive"))
    )
    (net (code "23") (name "HB2B") (class "Default")
      (node (ref "D11") (pin "C") (pinfunction "C_C") (pintype "passive"))
      (node (ref "D7") (pin "A") (pinfunction "A_A") (pintype "passive"))
      (node (ref "IC1") (pin "14") (pinfunction "OUT4_14") (pintype "output"))
      (node (ref "J3") (pin "4") (pinfunction "4_4") (pintype "passive"))
    )
    (net (code "24") (name "HB3A") (class "Default")
      (node (ref "D17") (pin "A") (pinfunction "A_A") (pintype "passive"))
      (node (ref "D21") (pin "C") (pinfunction "C_C") (pintype "passive"))
      (node (ref "IC2") (pin "2") (pinfunction "OUT1_2") (pintype "output"))
      (node (ref "J6") (pin "4") (pinfunction "4_4") (pintype "passive"))
    )
    (net (code "25") (name "HB3B") (class "Default")
      (node (ref "D18") (pin "A") (pinfunction "A_A") (pintype "passive"))
      (node (ref "D22") (pin "C") (pinfunction "C_C") (pintype "passive"))
      (node (ref "IC2") (pin "3") (pinfunction "OUT2_3") (pintype "output"))
      (node (ref "J6") (pin "3") (pinfunction "3_3") (pintype "passive"))
    )
    (net (code "26") (name "HB4A") (class "Default")
      (node (ref "D19") (pin "A") (pinfunction "A_A") (pintype "passive"))
      (node (ref "D23") (pin "C") (pinfunction "C_C") (pintype "passive"))
      (node (ref "IC2") (pin "13") (pinfunction "OUT3_13") (pintype "output"))
      (node (ref "J6") (pin "2") (pinfunction "2_2") (pintype "passive"))
    )
    (net (code "27") (name "HB4B") (class "Default")
      (node (ref "D20") (pin "A") (pinfunction "A_A") (pintype "passive"))
      (node (ref "D24") (pin "C") (pinfunction "C_C") (pintype "passive"))
      (node (ref "IC2") (pin "14") (pinfunction "OUT4_14") (pintype "output"))
      (node (ref "J6") (pin "1") (pinfunction "1_1") (pintype "passive"))
    )
    (net (code "28") (name "HEN") (class "Default")
      (node (ref "IC1") (pin "11") (pinfunction "ENABLE_B_11") (pintype "input"))
      (node (ref "IC1") (pin "6") (pinfunction "ENABLE_A_6") (pintype "input"))
      (node (ref "IC2") (pin "11") (pinfunction "ENABLE_B_11") (pintype "input"))
      (node (ref "IC2") (pin "6") (pinfunction "ENABLE_A_6") (pintype "input"))
      (node (ref "J4") (pin "17") (pinfunction "17_17") (pintype "passive"))
      (node (ref "U$1") (pin "TCK") (pinfunction "TCK/13_TCK") (pintype "bidirectional"))
    )
    (net (code "29") (name "LDO") (class "Default")
      (node (ref "J15") (pin "2") (pinfunction "2_2") (pintype "passive"))
      (node (ref "R12") (pin "P$2") (pinfunction "2_P$2") (pintype "passive"))
    )
    (net (code "30") (name "LED") (class "Default")
      (node (ref "J4") (pin "9") (pinfunction "9_9") (pintype "passive"))
      (node (ref "Q2") (pin "S") (pinfunction "S_S") (pintype "bidirectional"))
      (node (ref "R7") (pin "P$2") (pinfunction "2_P$2") (pintype "passive"))
      (node (ref "U$1") (pin "19") (pinfunction "19/MISO_19") (pintype "bidirectional"))
    )
    (net (code "31") (name "Net-(C2-Pad2)") (class "Default")
      (node (ref "C2") (pin "2") (pinfunction "2_2") (pintype "passive"))
      (node (ref "D1") (pin "C") (pinfunction "C_C") (pintype "passive"))
      (node (ref "PWR1") (pin "VIN") (pinfunction "VIN_VIN") (pintype "bidirectional"))
    )
    (net (code "32") (name "Net-(DR1-A1)") (class "Default")
      (node (ref "DR1") (pin "12") (pinfunction "A1_12") (pintype "bidirectional"))
      (node (ref "J2") (pin "2") (pinfunction "2_2") (pintype "passive"))
    )
    (net (code "33") (name "Net-(DR1-A2)") (class "Default")
      (node (ref "DR1") (pin "11") (pinfunction "A2_11") (pintype "bidirectional"))
      (node (ref "J2") (pin "1") (pinfunction "1_1") (pintype "passive"))
    )
    (net (code "34") (name "Net-(DR1-B1)") (class "Default")
      (node (ref "DR1") (pin "13") (pinfunction "B1_13") (pintype "bidirectional"))
      (node (ref "J2") (pin "3") (pinfunction "3_3") (pintype "passive"))
    )
    (net (code "35") (name "Net-(DR1-B2)") (class "Default")
      (node (ref "DR1") (pin "14") (pinfunction "B2_14") (pintype "bidirectional"))
      (node (ref "J2") (pin "4") (pinfunction "4_4") (pintype "passive"))
    )
    (net (code "36") (name "Net-(DR1-M0)") (class "Default")
      (node (ref "DR1") (pin "2") (pinfunction "M0_2") (pintype "bidirectional"))
      (node (ref "R2") (pin "P$1") (pinfunction "1_P$1") (pintype "passive"))
      (node (ref "SW2") (pin "3") (pinfunction "3_3") (pintype "passive"))
    )
    (net (code "37") (name "Net-(DR1-M1)") (class "Default")
      (node (ref "DR1") (pin "3") (pinfunction "M1_3") (pintype "bidirectional"))
      (node (ref "R3") (pin "P$1") (pinfunction "1_P$1") (pintype "passive"))
      (node (ref "SW2") (pin "2") (pinfunction "2_2") (pintype "passive"))
    )
    (net (code "38") (name "Net-(DR1-M2)") (class "Default")
      (node (ref "DR1") (pin "4") (pinfunction "M2_4") (pintype "bidirectional"))
      (node (ref "R4") (pin "P$1") (pinfunction "1_P$1") (pintype "passive"))
      (node (ref "SW2") (pin "1") (pinfunction "1_1") (pintype "passive"))
    )
    (net (code "39") (name "Net-(DR1-~{RST})") (class "Default")
      (node (ref "DR1") (pin "5") (pinfunction "~{RST}_5") (pintype "bidirectional"))
      (node (ref "DR1") (pin "6") (pinfunction "~{SLP}_6") (pintype "bidirectional"))
    )
    (net (code "40") (name "Net-(J10-Pad1)") (class "Default")
      (node (ref "J10") (pin "1") (pinfunction "1_1") (pintype "bidirectional"))
      (node (ref "J9") (pin "6") (pinfunction "6_6") (pintype "passive"))
    )
    (net (code "41") (name "Net-(J10-Pad3)") (class "Default")
      (node (ref "J10") (pin "3") (pinfunction "3_3") (pintype "bidirectional"))
      (node (ref "J9") (pin "5") (pinfunction "5_5") (pintype "passive"))
    )
    (net (code "42") (name "Net-(J10-Pad5)") (class "Default")
      (node (ref "J10") (pin "5") (pinfunction "5_5") (pintype "bidirectional"))
      (node (ref "J9") (pin "4") (pinfunction "4_4") (pintype "passive"))
    )
    (net (code "43") (name "Net-(J18-Pad3)") (class "Default")
      (node (ref "J18") (pin "3") (pinfunction "3_3") (pintype "passive"))
      (node (ref "J20") (pin "3") (pinfunction "3_3") (pintype "passive"))
    )
    (net (code "44") (name "Net-(J18-Pad4)") (class "Default")
      (node (ref "J18") (pin "4") (pinfunction "4_4") (pintype "passive"))
      (node (ref "J20") (pin "2") (pinfunction "2_2") (pintype "passive"))
    )
    (net (code "45") (name "Net-(J18-Pad5)") (class "Default")
      (node (ref "J18") (pin "5") (pinfunction "5_5") (pintype "passive"))
      (node (ref "J20") (pin "1") (pinfunction "1_1") (pintype "passive"))
    )
    (net (code "46") (name "Net-(R5-1)") (class "Default")
      (node (ref "Q7") (pin "D") (pinfunction "D_D") (pintype "bidirectional"))
      (node (ref "R5") (pin "P$1") (pinfunction "1_P$1") (pintype "passive"))
      (node (ref "R6") (pin "P$1") (pinfunction "1_P$1") (pintype "passive"))
    )
    (net (code "47") (name "Net-(R6-2)") (class "Default")
      (node (ref "Q1") (pin "G") (pinfunction "G_G") (pintype "passive"))
      (node (ref "R6") (pin "P$2") (pinfunction "2_P$2") (pintype "passive"))
    )
    (net (code "48") (name "Net-(R11-2)") (class "Default")
      (node (ref "Q2") (pin "D") (pinfunction "D_D") (pintype "bidirectional"))
      (node (ref "R11") (pin "P$2") (pinfunction "2_P$2") (pintype "passive"))
      (node (ref "R12") (pin "P$1") (pinfunction "1_P$1") (pintype "passive"))
    )
    (net (code "49") (name "Net-(R13-1)") (class "Default")
      (node (ref "D12") (pin "A") (pinfunction "A_A") (pintype "passive"))
      (node (ref "Q7") (pin "G") (pinfunction "G_G") (pintype "bidirectional"))
      (node (ref "R13") (pin "P$1") (pinfunction "1_P$1") (pintype "passive"))
      (node (ref "R23") (pin "P$2") (pinfunction "2_P$2") (pintype "passive"))
    )
    (net (code "50") (name "Net-(R14-2)") (class "Default")
      (node (ref "J10") (pin "2") (pinfunction "2_2") (pintype "bidirectional"))
      (node (ref "J10") (pin "4") (pinfunction "4_4") (pintype "bidirectional"))
      (node (ref "J10") (pin "6") (pinfunction "6_6") (pintype "bidirectional"))
      (node (ref "R14") (pin "P$2") (pinfunction "2_P$2") (pintype "passive"))
    )
    (net (code "51") (name "Net-(R17-2)") (class "Default")
      (node (ref "J17") (pin "1") (pinfunction "1_1") (pintype "passive"))
      (node (ref "R17") (pin "P$2") (pinfunction "2_P$2") (pintype "passive"))
    )
    (net (code "52") (name "Net-(R20-1)") (class "Default")
      (node (ref "Q8") (pin "D") (pinfunction "D_D") (pintype "bidirectional"))
      (node (ref "R20") (pin "P$1") (pinfunction "1_P$1") (pintype "passive"))
      (node (ref "R21") (pin "P$1") (pinfunction "1_P$1") (pintype "passive"))
    )
    (net (code "53") (name "Net-(R21-2)") (class "Default")
      (node (ref "Q3") (pin "G") (pinfunction "G_G") (pintype "passive"))
      (node (ref "R21") (pin "P$2") (pinfunction "2_P$2") (pintype "passive"))
    )
    (net (code "54") (name "Net-(R22-1)") (class "Default")
      (node (ref "D14") (pin "A") (pinfunction "A_A") (pintype "passive"))
      (node (ref "Q8") (pin "G") (pinfunction "G_G") (pintype "bidirectional"))
      (node (ref "R22") (pin "P$1") (pinfunction "1_P$1") (pintype "passive"))
      (node (ref "R24") (pin "P$2") (pinfunction "2_P$2") (pintype "passive"))
    )
    (net (code "55") (name "Net-(R25-1)") (class "Default")
      (node (ref "Q6") (pin "D") (pinfunction "D_D") (pintype "bidirectional"))
      (node (ref "R25") (pin "P$1") (pinfunction "1_P$1") (pintype "passive"))
    )
    (net (code "56") (name "Net-(R25-2)") (class "Default")
      (node (ref "R25") (pin "P$2") (pinfunction "2_P$2") (pintype "passive"))
      (node (ref "SG1") (pin "-") (pinfunction "-_-") (pintype "passive"))
    )
    (net (code "57") (name "Net-(R26-2)") (class "Default")
      (node (ref "Q6") (pin "G") (pinfunction "G_G") (pintype "bidirectional"))
      (node (ref "R26") (pin "P$2") (pinfunction "2_P$2") (pintype "passive"))
    )
    (net (code "58") (name "Net-(R27-1)") (class "Default")
      (node (ref "J18") (pin "7") (pinfunction "7_7") (pintype "passive"))
      (node (ref "R27") (pin "P$1") (pinfunction "1_P$1") (pintype "passive"))
    )
    (net (code "59") (name "Net-(R28-1)") (class "Default")
      (node (ref "J18") (pin "6") (pinfunction "6_6") (pintype "passive"))
      (node (ref "R28") (pin "P$1") (pinfunction "1_P$1") (pintype "passive"))
    )
    (net (code "60") (name "P1") (class "Default")
      (node (ref "D12") (pin "C") (pinfunction "C_C") (pintype "passive"))
      (node (ref "J5") (pin "9") (pinfunction "9_9") (pintype "passive"))
      (node (ref "U$1") (pin "17") (pinfunction "17_17") (pintype "bidirectional"))
    )
    (net (code "61") (name "P2") (class "Default")
      (node (ref "D14") (pin "C") (pinfunction "C_C") (pintype "passive"))
      (node (ref "J4") (pin "5") (pinfunction "5_5") (pintype "passive"))
      (node (ref "U$1") (pin "26") (pinfunction "26_26") (pintype "bidirectional"))
    )
    (net (code "62") (name "PHIN") (class "Default")
      (node (ref "D5") (pin "C") (pinfunction "C_C") (pintype "passive"))
      (node (ref "J4") (pin "6") (pinfunction "6_6") (pintype "passive"))
      (node (ref "R14") (pin "P$1") (pinfunction "1_P$1") (pintype "passive"))
      (node (ref "R15") (pin "P$1") (pinfunction "1_P$1") (pintype "passive"))
      (node (ref "U$1") (pin "SVN") (pinfunction "SVN/39_SVN") (pintype "bidirectional"))
    )
    (net (code "63") (name "PP1") (class "Default")
      (node (ref "D2") (pin "A") (pinfunction "A_A") (pintype "passive"))
      (node (ref "J19") (pin "4") (pinfunction "4_4") (pintype "passive"))
      (node (ref "Q1") (pin "D") (pinfunction "D_D") (pintype "passive"))
    )
    (net (code "64") (name "PP2") (class "Default")
      (node (ref "D13") (pin "A") (pinfunction "A_A") (pintype "passive"))
      (node (ref "J19") (pin "2") (pinfunction "2_2") (pintype "passive"))
      (node (ref "Q3") (pin "D") (pinfunction "D_D") (pintype "passive"))
    )
    (net (code "65") (name "RX") (class "Default")
      (node (ref "J5") (pin "3") (pinfunction "3_3") (pintype "passive"))
      (node (ref "U$1") (pin "RX0") (pinfunction "RX0/3_RX0") (pintype "bidirectional"))
    )
    (net (code "66") (name "SCL") (class "Default")
      (node (ref "J5") (pin "5") (pinfunction "5_5") (pintype "passive"))
      (node (ref "J7") (pin "4") (pinfunction "4_4") (pintype "passive"))
      (node (ref "Q4") (pin "S") (pinfunction "S_S") (pintype "bidirectional"))
      (node (ref "R8") (pin "P$2") (pinfunction "2_P$2") (pintype "passive"))
      (node (ref "U$1") (pin "22") (pinfunction "22/SCL_22") (pintype "bidirectional"))
    )
    (net (code "67") (name "SCL5") (class "Default")
      (node (ref "J8") (pin "4") (pinfunction "4_4") (pintype "passive"))
      (node (ref "Q4") (pin "D") (pinfunction "D_D") (pintype "bidirectional"))
      (node (ref "R10") (pin "P$2") (pinfunction "2_P$2") (pintype "passive"))
    )
    (net (code "68") (name "SD0") (class "Default")
      (node (ref "J5") (pin "19") (pinfunction "19_19") (pintype "passive"))
      (node (ref "U$1") (pin "SD0") (pinfunction "SD0/7_SD0") (pintype "bidirectional"))
    )
    (net (code "69") (name "SD1") (class "Default")
      (node (ref "J5") (pin "18") (pinfunction "18_18") (pintype "passive"))
      (node (ref "U$1") (pin "SD1") (pinfunction "SD1/8_SD1") (pintype "bidirectional"))
    )
    (net (code "70") (name "SD2") (class "Default")
      (node (ref "J4") (pin "18") (pinfunction "18_18") (pintype "passive"))
      (node (ref "U$1") (pin "SD2") (pinfunction "SD2/9_SD2") (pintype "bidirectional"))
    )
    (net (code "71") (name "SD3") (class "Default")
      (node (ref "J4") (pin "19") (pinfunction "19_19") (pintype "passive"))
      (node (ref "U$1") (pin "SD3") (pinfunction "SD3/10_SD3") (pintype "bidirectional"))
    )
    (net (code "72") (name "SDA") (class "Default")
      (node (ref "J5") (pin "7") (pinfunction "7_7") (pintype "passive"))
      (node (ref "J7") (pin "3") (pinfunction "3_3") (pintype "passive"))
      (node (ref "Q5") (pin "S") (pinfunction "S_S") (pintype "bidirectional"))
      (node (ref "R1") (pin "P$2") (pinfunction "2_P$2") (pintype "passive"))
      (node (ref "U$1") (pin "21") (pinfunction "21/SDA_21") (pintype "bidirectional"))
    )
    (net (code "73") (name "SDA5") (class "Default")
      (node (ref "J8") (pin "3") (pinfunction "3_3") (pintype "passive"))
      (node (ref "Q5") (pin "D") (pinfunction "D_D") (pintype "bidirectional"))
      (node (ref "R9") (pin "P$2") (pinfunction "2_P$2") (pintype "passive"))
    )
    (net (code "74") (name "SDIR") (class "Default")
      (node (ref "DR1") (pin "8") (pinfunction "DIR_8") (pintype "bidirectional"))
      (node (ref "J5") (pin "8") (pinfunction "8_8") (pintype "passive"))
      (node (ref "U$1") (pin "32") (pinfunction "32_32") (pintype "bidirectional"))
    )
    (net (code "75") (name "SERVO1") (class "Default")
      (node (ref "J5") (pin "16") (pinfunction "16_16") (pintype "passive"))
      (node (ref "R17") (pin "P$1") (pinfunction "1_P$1") (pintype "passive"))
      (node (ref "U$1") (pin "2") (pinfunction "2_2") (pintype "bidirectional"))
    )
    (net (code "76") (name "STEP") (class "Default")
      (node (ref "DR1") (pin "7") (pinfunction "STEP_7") (pintype "bidirectional"))
      (node (ref "J5") (pin "6") (pinfunction "6_6") (pintype "passive"))
      (node (ref "U$1") (pin "25") (pinfunction "25_25") (pintype "bidirectional"))
    )
    (net (code "77") (name "TEMP") (class "Default")
      (node (ref "J11") (pin "2") (pinfunction "2_2") (pintype "passive"))
      (node (ref "J12") (pin "2") (pinfunction "2_2") (pintype "passive"))
      (node (ref "J13") (pin "2") (pinfunction "2_2") (pintype "passive"))
      (node (ref "J4") (pin "3") (pinfunction "3_3") (pintype "passive"))
      (node (ref "R16") (pin "P$2") (pinfunction "2_P$2") (pintype "passive"))
      (node (ref "U$1") (pin "SVP") (pinfunction "SVP/36_SVP") (pintype "bidirectional"))
    )
    (net (code "78") (name "TX") (class "Default")
      (node (ref "J5") (pin "1") (pinfunction "1_1") (pintype "passive"))
      (node (ref "U$1") (pin "TX0") (pinfunction "TX0/1_TX0") (pintype "bidirectional"))
    )
    (net (code "79") (name "VCC") (class "Default")
      (node (ref "C10") (pin "+") (pinfunction "+_+") (pintype "passive"))
      (node (ref "C4") (pin "+") (pinfunction "+_+") (pintype "passive"))
      (node (ref "C6") (pin "+") (pinfunction "+_+") (pintype "passive"))
      (node (ref "D1") (pin "A") (pinfunction "A_A") (pintype "passive"))
      (node (ref "D13") (pin "C") (pinfunction "C_C") (pintype "passive"))
      (node (ref "D17") (pin "C") (pinfunction "C_C") (pintype "passive"))
      (node (ref "D18") (pin "C") (pinfunction "C_C") (pintype "passive"))
      (node (ref "D19") (pin "C") (pinfunction "C_C") (pintype "passive"))
      (node (ref "D2") (pin "C") (pinfunction "C_C") (pintype "passive"))
      (node (ref "D20") (pin "C") (pinfunction "C_C") (pintype "passive"))
      (node (ref "D3") (pin "C") (pinfunction "C_C") (pintype "passive"))
      (node (ref "D4") (pin "C") (pinfunction "C_C") (pintype "passive"))
      (node (ref "D6") (pin "C") (pinfunction "C_C") (pintype "passive"))
      (node (ref "D7") (pin "C") (pinfunction "C_C") (pintype "passive"))
      (node (ref "DR1") (pin "16") (pinfunction "VMOT_16") (pintype "bidirectional"))
      (node (ref "IC1") (pin "4") (pinfunction "VS_4") (pintype "power_in"))
      (node (ref "IC2") (pin "4") (pinfunction "VS_4") (pintype "power_in"))
      (node (ref "J1") (pin "3") (pinfunction "3_3") (pintype "passive"))
      (node (ref "J1") (pin "4") (pinfunction "4_4") (pintype "passive"))
      (node (ref "J16") (pin "4") (pinfunction "4_4") (pintype "passive"))
      (node (ref "J19") (pin "1") (pinfunction "1_1") (pintype "passive"))
      (node (ref "J19") (pin "3") (pinfunction "3_3") (pintype "passive"))
      (node (ref "JACK") (pin "PWR") (pinfunction "PWR_PWR") (pintype "bidirectional"))
      (node (ref "R20") (pin "P$2") (pinfunction "2_P$2") (pintype "passive"))
      (node (ref "R5") (pin "P$2") (pinfunction "2_P$2") (pintype "passive"))
    )
    (net (code "80") (name "unconnected-(U$1-NC-PadNC.1)") (class "Default")
      (node (ref "U$1") (pin "NC.1") (pinfunction "NC_NC.1") (pintype "bidirectional"))
    )
    (net (code "81") (name "unconnected-(U$1-N{slash}C-PadNC)") (class "Default")
      (node (ref "U$1") (pin "NC") (pinfunction "N/C_NC") (pintype "bidirectional"))
    )
  )
)
